# TPA6120A2_Headphone_Amp.net
KiCad netlist of a schematic drawn in Altium Designer
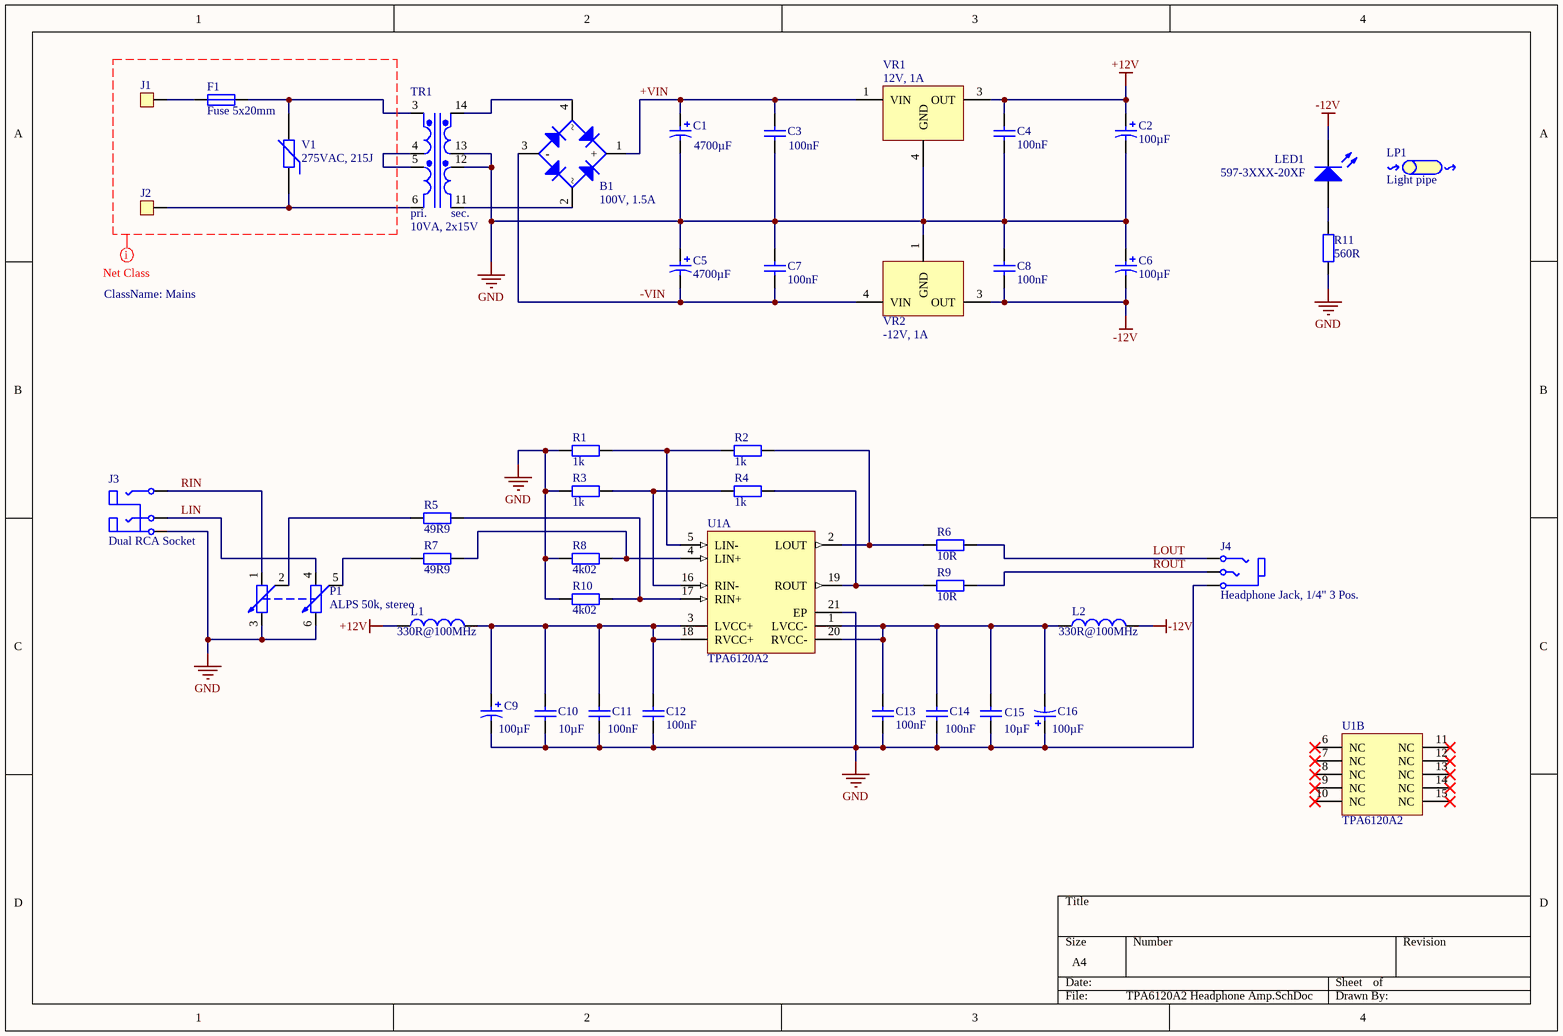
[diagram p0: TPA6120A2 Headphone Amp.SchDoc]

(export (version "E")
  (design (tool "Eeschema 10.0.6"))
  (components
    (comp (ref "B1")
      (value "100V, 1.5A")
      (footprint "WOG")
      (description "RECTIFIER BRIDGE 1.5A 100V WOG")
      (fields
        (field (name "PART NUMBER") "W01G-E4/51")
        (field (name "MANUFACTURER") "Vishay Semiconductor Diodes Division")
      )
      (libsource (lib "SVNDatabase_AK") (part "Bridge Rectifier"))
    )
    (comp (ref "C1")
      (value "4700µF")
      (footprint "CAP POL 16x25 RM 7.5MM")
      (description "CAP ALUM 4700UF 20% 25V RADIAL")
      (fields (field (name "PART NUMBER") "UVY1E472MHD") (field (name "MANUFACTURER") "Nichicon"))
      (libsource (lib "SVNDatabase_AK") (part "Cap Pol"))
    )
    (comp (ref "C2")
      (value "100µF")
      (footprint "cap pol 10x12.5mm rm 5mm")
      (description "CAP ALUM 100UF 20% 63V RADIAL")
      (fields
        (field (name "PART NUMBER") "EEU-FC1J101")
        (field (name "MANUFACTURER") "Panasonic Electronic Components")
      )
      (libsource (lib "SVNDatabase_AK") (part "Cap Pol"))
    )
    (comp (ref "C3")
      (value "100nF")
      (footprint "CAP0805_M")
      (description "CAP CER 0.1UF 50V 10% X7R 0805")
      (fields (field (name "PART NUMBER") "C0805C104K5RACTU") (field (name "MANUFACTURER") "Kemet"))
      (libsource (lib "SVNDatabase_AK") (part "CAP"))
    )
    (comp (ref "C4")
      (value "100nF")
      (footprint "CAP0805_M")
      (description "CAP CER 0.1UF 50V 10% X7R 0805")
      (fields (field (name "PART NUMBER") "C0805C104K5RACTU") (field (name "MANUFACTURER") "Kemet"))
      (libsource (lib "SVNDatabase_AK") (part "CAP"))
    )
    (comp (ref "C5")
      (value "4700µF")
      (footprint "CAP POL 16x25 RM 7.5MM")
      (description "CAP ALUM 4700UF 20% 25V RADIAL")
      (fields (field (name "PART NUMBER") "UVY1E472MHD") (field (name "MANUFACTURER") "Nichicon"))
      (libsource (lib "SVNDatabase_AK") (part "Cap Pol"))
    )
    (comp (ref "C6")
      (value "100µF")
      (footprint "cap pol 10x12.5mm rm 5mm")
      (description "CAP ALUM 100UF 20% 63V RADIAL")
      (fields
        (field (name "PART NUMBER") "EEU-FC1J101")
        (field (name "MANUFACTURER") "Panasonic Electronic Components")
      )
      (libsource (lib "SVNDatabase_AK") (part "Cap Pol"))
    )
    (comp (ref "C7")
      (value "100nF")
      (footprint "CAP0805_M")
      (description "CAP CER 0.1UF 50V 10% X7R 0805")
      (fields (field (name "PART NUMBER") "C0805C104K5RACTU") (field (name "MANUFACTURER") "Kemet"))
      (libsource (lib "SVNDatabase_AK") (part "CAP"))
    )
    (comp (ref "C8")
      (value "100nF")
      (footprint "CAP0805_M")
      (description "CAP CER 0.1UF 50V 10% X7R 0805")
      (fields (field (name "PART NUMBER") "C0805C104K5RACTU") (field (name "MANUFACTURER") "Kemet"))
      (libsource (lib "SVNDatabase_AK") (part "CAP"))
    )
    (comp (ref "C9")
      (value "100µF")
      (footprint "cap pol 10x12.5mm rm 5mm")
      (description "CAP ALUM 100UF 20% 63V RADIAL")
      (fields
        (field (name "PART NUMBER") "EEU-FC1J101")
        (field (name "MANUFACTURER") "Panasonic Electronic Components")
      )
      (libsource (lib "SVNDatabase_AK") (part "Cap Pol"))
    )
    (comp (ref "C10")
      (value "10µF")
      (footprint "CAP1210_M")
      (description "CAP CER 10UF 50V X7R 1210")
      (fields (field (name "PART NUMBER") "C1210C106K5RACTU") (field (name "MANUFACTURER") "Kemet"))
      (libsource (lib "SVNDatabase_AK") (part "CAP"))
    )
    (comp (ref "C11")
      (value "100nF")
      (footprint "CAP0805_M")
      (description "CAP CER 0.1UF 50V 10% X7R 0805")
      (fields (field (name "PART NUMBER") "C0805C104K5RACTU") (field (name "MANUFACTURER") "Kemet"))
      (libsource (lib "SVNDatabase_AK") (part "CAP"))
    )
    (comp (ref "C12")
      (value "100nF")
      (footprint "CAP0805_M")
      (description "CAP CER 0.1UF 50V 10% X7R 0805")
      (fields (field (name "PART NUMBER") "C0805C104K5RACTU") (field (name "MANUFACTURER") "Kemet"))
      (libsource (lib "SVNDatabase_AK") (part "CAP"))
    )
    (comp (ref "C13")
      (value "100nF")
      (footprint "CAP0805_M")
      (description "CAP CER 0.1UF 50V 10% X7R 0805")
      (fields (field (name "PART NUMBER") "C0805C104K5RACTU") (field (name "MANUFACTURER") "Kemet"))
      (libsource (lib "SVNDatabase_AK") (part "CAP"))
    )
    (comp (ref "C14")
      (value "100nF")
      (footprint "CAP0805_M")
      (description "CAP CER 0.1UF 50V 10% X7R 0805")
      (fields (field (name "PART NUMBER") "C0805C104K5RACTU") (field (name "MANUFACTURER") "Kemet"))
      (libsource (lib "SVNDatabase_AK") (part "CAP"))
    )
    (comp (ref "C15")
      (value "10µF")
      (footprint "CAP1210_M")
      (description "CAP CER 10UF 50V X7R 1210")
      (fields (field (name "PART NUMBER") "C1210C106K5RACTU") (field (name "MANUFACTURER") "Kemet"))
      (libsource (lib "SVNDatabase_AK") (part "CAP"))
    )
    (comp (ref "C16")
      (value "100µF")
      (footprint "cap pol 10x12.5mm rm 5mm")
      (description "CAP ALUM 100UF 20% 63V RADIAL")
      (fields
        (field (name "PART NUMBER") "EEU-FC1J101")
        (field (name "MANUFACTURER") "Panasonic Electronic Components")
      )
      (libsource (lib "SVNDatabase_AK") (part "Cap Pol"))
    )
    (comp (ref "F1")
      (value "Fuse 5x20mm")
      (footprint "0031.8201")
      (description "FUSE BLOK CARTRIDGE 500V 10A PCB")
      (fields (field (name "PART NUMBER") "0031.8201") (field (name "MANUFACTURER") "Schurter Inc."))
      (libsource (lib "SVNDatabase_AK") (part "Fuse"))
    )
    (comp (ref "J1")
      (value "~")
      (footprint "928814-1")
      (description "CONN QC TAB 0.250 SOLDER")
      (fields
        (field (name "PART NUMBER") "928814-1")
        (field (name "MANUFACTURER") "TE Connectivity AMP Connectors")
      )
      (libsource (lib "SVNDatabase_AK") (part "Header 1"))
    )
    (comp (ref "J2")
      (value "~")
      (footprint "928814-1")
      (description "CONN QC TAB 0.250 SOLDER")
      (fields
        (field (name "PART NUMBER") "928814-1")
        (field (name "MANUFACTURER") "TE Connectivity AMP Connectors")
      )
      (libsource (lib "SVNDatabase_AK") (part "Header 1"))
    )
    (comp (ref "J3")
      (value "Dual RCA Socket")
      (footprint "PJRAS1X2S__X")
      (description "PHONO JACK 2POS R/A RED/WHT")
      (fields (field (name "PART NUMBER") "PJRAS1X2S01X") (field (name "MANUFACTURER") "Switchcraft Inc."))
      (libsource (lib "SVNDatabase_AK") (part "Dual RCA Jack"))
    )
    (comp (ref "J4")
      (value "Headphone Jack, 1/4\" 3 Pos.")
      (footprint "RA49B")
      (description "CONN JACK R/A 3-COND DBL OPEN")
      (fields (field (name "PART NUMBER") "RA49B12B") (field (name "MANUFACTURER") "Switchcraft Inc."))
      (libsource (lib "SVNDatabase_AK") (part "Headphone Jack"))
    )
    (comp (ref "L1")
      (value "330R@100MHz")
      (footprint "INDC2012X14N")
      (description "FERRITE CHIP 330 OHM 2.5A 0805")
      (fields (field (name "PART NUMBER") "MPZ2012S331AT000") (field (name "MANUFACTURER") "TDK Corporation"))
      (libsource (lib "SVNDatabase_AK") (part "Inductor"))
    )
    (comp (ref "L2")
      (value "330R@100MHz")
      (footprint "INDC2012X14N")
      (description "FERRITE CHIP 330 OHM 2.5A 0805")
      (fields (field (name "PART NUMBER") "MPZ2012S331AT000") (field (name "MANUFACTURER") "TDK Corporation"))
      (libsource (lib "SVNDatabase_AK") (part "Inductor"))
    )
    (comp (ref "LED1")
      (value "597-3XXX-20XF")
      (footprint "597-3XXX-20XF")
      (description "LED RED CLEAR 2PLCC SMD")
      (fields (field (name "PART NUMBER") "597-3001-202F") (field (name "MANUFACTURER") "Dialight"))
      (libsource (lib "SVNDatabase_AK") (part "LED"))
    )
    (comp (ref "LP1")
      (value "Light pipe")
      (footprint "515-1049F")
      (description "LIGHT PIPE SGL ELEMENT")
      (fields (field (name "PART NUMBER") "5151049F") (field (name "MANUFACTURER") "Dialight"))
      (libsource (lib "SVNDatabase_AK") (part "Lightpipe"))
    )
    (comp (ref "P1")
      (value "ALPS 50k, stereo")
      (footprint "ALPS RK27112")
      (description "Pot, Stereo")
      (fields (field (name "PART NUMBER") "ALPS RK27112-F25-C0-A203"))
      (libsource (lib "SVNDatabase_AK") (part "Pot Stereo"))
    )
    (comp (ref "R1")
      (value "1k")
      (footprint "RES0805_M")
      (description "RES SMD 1K OHM 0.1% 1/8W 0805")
      (fields (field (name "PART NUMBER") "TNPW08051K00BEEA") (field (name "MANUFACTURER") "Vishay Dale"))
      (libsource (lib "SVNDatabase_AK") (part "RES"))
    )
    (comp (ref "R2")
      (value "1k")
      (footprint "RES1206_M")
      (description "RES SMD 1K OHM 0.1% 1/4W 1206")
      (fields (field (name "PART NUMBER") "TNPW12061K00BEEA") (field (name "MANUFACTURER") "Vishay Dale"))
      (libsource (lib "") (part "RES_2"))
    )
    (comp (ref "R3")
      (value "1k")
      (footprint "RES0805_M")
      (description "RES SMD 1K OHM 0.1% 1/8W 0805")
      (fields (field (name "PART NUMBER") "TNPW08051K00BEEA") (field (name "MANUFACTURER") "Vishay Dale"))
      (libsource (lib "SVNDatabase_AK") (part "RES"))
    )
    (comp (ref "R4")
      (value "1k")
      (footprint "RES1206_M")
      (description "RES SMD 1K OHM 0.1% 1/4W 1206")
      (fields (field (name "PART NUMBER") "TNPW12061K00BEEA") (field (name "MANUFACTURER") "Vishay Dale"))
      (libsource (lib "") (part "RES_2"))
    )
    (comp (ref "R5")
      (value "49R9")
      (footprint "RES0805_M")
      (description "RES SMD 49.9 OHM 0.1% 1/8W 0805")
      (fields (field (name "PART NUMBER") "TNPW080549R9BEEA") (field (name "MANUFACTURER") "Vishay Dale"))
      (libsource (lib "SVNDatabase_AK") (part "RES"))
    )
    (comp (ref "R6")
      (value "10R")
      (footprint "RES1206_M")
      (description "RES SMD 10 OHM 0.1% 0.4W 1206")
      (fields
        (field (name "PART NUMBER") "PAT1206E10R0BST1")
        (field (name "MANUFACTURER") "Vishay Thin Film")
      )
      (libsource (lib "SVNDatabase_AK") (part "RES"))
    )
    (comp (ref "R7")
      (value "49R9")
      (footprint "RES0805_M")
      (description "RES SMD 49.9 OHM 0.1% 1/8W 0805")
      (fields (field (name "PART NUMBER") "TNPW080549R9BEEA") (field (name "MANUFACTURER") "Vishay Dale"))
      (libsource (lib "SVNDatabase_AK") (part "RES"))
    )
    (comp (ref "R8")
      (value "4k02")
      (footprint "RES0805_M")
      (description "RES SMD 4.02K OHM 0.1% 1/5W 0805")
      (fields
        (field (name "PART NUMBER") "MCU0805MD4021BP100")
        (field (name "MANUFACTURER") "Vishay Beyschlag")
      )
      (libsource (lib "SVNDatabase_AK") (part "RES"))
    )
    (comp (ref "R9")
      (value "10R")
      (footprint "RES1206_M")
      (description "RES SMD 10 OHM 0.1% 0.4W 1206")
      (fields
        (field (name "PART NUMBER") "PAT1206E10R0BST1")
        (field (name "MANUFACTURER") "Vishay Thin Film")
      )
      (libsource (lib "SVNDatabase_AK") (part "RES"))
    )
    (comp (ref "R10")
      (value "4k02")
      (footprint "RES0805_M")
      (description "RES SMD 4.02K OHM 0.1% 1/5W 0805")
      (fields
        (field (name "PART NUMBER") "MCU0805MD4021BP100")
        (field (name "MANUFACTURER") "Vishay Beyschlag")
      )
      (libsource (lib "SVNDatabase_AK") (part "RES"))
    )
    (comp (ref "R11")
      (value "560R")
      (footprint "RES1206_M")
      (description "RES SMD 560 OHM 1% 1/2W 1206")
      (fields (field (name "PART NUMBER") "CRCW1206560RFKEAHP") (field (name "MANUFACTURER") "Vishay Dale"))
      (libsource (lib "") (part "RES_1"))
    )
    (comp (ref "TR1")
      (value "10VA, 2x15V")
      (footprint "Talema 10VA")
      (description "XFRMR TOROIDAL 10VA THRU HOLE")
      (fields
        (field (name "PART NUMBER") "Talema 70043k")
        (field (name "MANUFACTURER") "Acme Electric/Amveco/Actown")
      )
      (libsource (lib "SVNDatabase_AK") (part "Talema 70000 series"))
    )
    (comp (ref "U1")
      (value "TPA6120A2")
      (footprint "TI-DWP20-3730X2350TP_N")
      (description "IC AMP AUDIO .08W HIFI 20SOPWR")
      (fields (field (name "PART NUMBER") "TPA6120A2DWPR") (field (name "MANUFACTURER") "Texas Instruments"))
      (libsource (lib "SVNDatabase_AK") (part "TPA6120A2_DWP20"))
    )
    (comp (ref "V1")
      (value "275VAC, 215J")
      (footprint "S20K275E2")
      (description "VARISTOR 387V 10KA DISC 20MM")
      (fields (field (name "PART NUMBER") "S20K275E2") (field (name "MANUFACTURER") "EPCOS (TDK)"))
      (libsource (lib "SVNDatabase_AK") (part "Varistor"))
    )
    (comp (ref "VR1")
      (value "12V, 1A")
      (footprint "D2PAK")
      (description "IC REG LDO 12V 1.5A D2PAK")
      (fields (field (name "PART NUMBER") "7812") (field (name "MANUFACTURER") "STMicroelectronics"))
      (libsource (lib "SVNDatabase_AK") (part "VREG_POS_D2PAK"))
    )
    (comp (ref "VR2")
      (value "-12V, 1A")
      (footprint "D2PAK")
      (description "IC REG LDO -12V 1.5A D2PAK")
      (fields (field (name "PART NUMBER") "7912") (field (name "MANUFACTURER") "STMicroelectronics"))
      (libsource (lib "SVNDatabase_AK") (part "VREG_NEG_D2PAK"))
    )
  )
  (nets
    (net (code "1") (name "+12V") (class "Default")
      (node (ref "C2") (pin "1") (pinfunction "1_1") (pintype "passive"))
      (node (ref "C4") (pin "2") (pinfunction "2_2") (pintype "passive"))
      (node (ref "L1") (pin "1") (pinfunction "1_1") (pintype "passive"))
      (node (ref "VR1") (pin "3") (pinfunction "OUT_3") (pintype "power_in"))
    )
    (net (code "2") (name "-12V") (class "Default")
      (node (ref "C6") (pin "2") (pinfunction "2_2") (pintype "passive"))
      (node (ref "C8") (pin "1") (pinfunction "1_1") (pintype "passive"))
      (node (ref "L2") (pin "2") (pinfunction "2_2") (pintype "passive"))
      (node (ref "LED1") (pin "2") (pinfunction "K_2") (pintype "passive"))
      (node (ref "VR2") (pin "3") (pinfunction "OUT_3") (pintype "power_in"))
    )
    (net (code "3") (name "/+VIN") (class "Default")
      (node (ref "B1") (pin "1") (pinfunction "+_1") (pintype "passive"))
      (node (ref "C1") (pin "1") (pinfunction "1_1") (pintype "passive"))
      (node (ref "C3") (pin "2") (pinfunction "2_2") (pintype "passive"))
      (node (ref "VR1") (pin "1") (pinfunction "VIN_1") (pintype "power_in"))
    )
    (net (code "4") (name "/-VIN") (class "Default")
      (node (ref "B1") (pin "3") (pinfunction "-_3") (pintype "passive"))
      (node (ref "C5") (pin "2") (pinfunction "2_2") (pintype "passive"))
      (node (ref "C7") (pin "1") (pinfunction "1_1") (pintype "passive"))
      (node (ref "VR2") (pin "4") (pinfunction "VIN_4") (pintype "power_in"))
    )
    (net (code "5") (name "/LIN") (class "Default")
      (node (ref "J3") (pin "1") (pinfunction "1_1") (pintype "passive"))
      (node (ref "P1") (pin "4") (pinfunction "4_4") (pintype "passive"))
    )
    (net (code "6") (name "/LOUT") (class "Default")
      (node (ref "J4") (pin "2") (pinfunction "2_2") (pintype "passive"))
      (node (ref "R6") (pin "2") (pinfunction "2_2") (pintype "passive"))
    )
    (net (code "7") (name "/RIN") (class "Default")
      (node (ref "J3") (pin "2") (pinfunction "2_2") (pintype "passive"))
      (node (ref "P1") (pin "1") (pinfunction "1_1") (pintype "passive"))
    )
    (net (code "8") (name "/ROUT") (class "Default")
      (node (ref "J4") (pin "3") (pinfunction "3_3") (pintype "passive"))
      (node (ref "R9") (pin "2") (pinfunction "2_2") (pintype "passive"))
    )
    (net (code "9") (name "GND") (class "Default")
      (node (ref "C1") (pin "2") (pinfunction "2_2") (pintype "passive"))
      (node (ref "C10") (pin "1") (pinfunction "1_1") (pintype "passive"))
      (node (ref "C11") (pin "1") (pinfunction "1_1") (pintype "passive"))
      (node (ref "C12") (pin "1") (pinfunction "1_1") (pintype "passive"))
      (node (ref "C13") (pin "1") (pinfunction "1_1") (pintype "passive"))
      (node (ref "C14") (pin "1") (pinfunction "1_1") (pintype "passive"))
      (node (ref "C15") (pin "1") (pinfunction "1_1") (pintype "passive"))
      (node (ref "C16") (pin "1") (pinfunction "1_1") (pintype "passive"))
      (node (ref "C2") (pin "2") (pinfunction "2_2") (pintype "passive"))
      (node (ref "C3") (pin "1") (pinfunction "1_1") (pintype "passive"))
      (node (ref "C4") (pin "1") (pinfunction "1_1") (pintype "passive"))
      (node (ref "C5") (pin "1") (pinfunction "1_1") (pintype "passive"))
      (node (ref "C6") (pin "1") (pinfunction "1_1") (pintype "passive"))
      (node (ref "C7") (pin "2") (pinfunction "2_2") (pintype "passive"))
      (node (ref "C8") (pin "2") (pinfunction "2_2") (pintype "passive"))
      (node (ref "C9") (pin "2") (pinfunction "2_2") (pintype "passive"))
      (node (ref "J3") (pin "3") (pinfunction "3_3") (pintype "passive"))
      (node (ref "J4") (pin "1") (pinfunction "1_1") (pintype "passive"))
      (node (ref "P1") (pin "3") (pinfunction "3_3") (pintype "passive"))
      (node (ref "P1") (pin "6") (pinfunction "6_6") (pintype "passive"))
      (node (ref "R1") (pin "1") (pinfunction "1_1") (pintype "passive"))
      (node (ref "R10") (pin "1") (pinfunction "1_1") (pintype "passive"))
      (node (ref "R11") (pin "2") (pinfunction "2_2") (pintype "passive"))
      (node (ref "R3") (pin "1") (pinfunction "1_1") (pintype "passive"))
      (node (ref "R8") (pin "1") (pinfunction "1_1") (pintype "passive"))
      (node (ref "TR1") (pin "12") (pinfunction "Sek1-_12") (pintype "passive"))
      (node (ref "TR1") (pin "13") (pinfunction "Sek2+_13") (pintype "passive"))
      (node (ref "U1") (pin "21") (pinfunction "EP_21") (pintype "power_in"))
      (node (ref "VR1") (pin "4") (pinfunction "GND_4") (pintype "power_in"))
      (node (ref "VR2") (pin "1") (pinfunction "GND_1") (pintype "power_in"))
    )
    (net (code "10") (name "Net-(F1-Pad1)") (class "Default")
      (node (ref "F1") (pin "1") (pinfunction "1_1") (pintype "passive"))
      (node (ref "J1") (pin "1") (pinfunction "1_1") (pintype "passive"))
    )
    (net (code "11") (name "Net-(LED1-A)") (class "Default")
      (node (ref "LED1") (pin "1") (pinfunction "A_1") (pintype "passive"))
      (node (ref "R11") (pin "1") (pinfunction "1_1") (pintype "passive"))
    )
    (net (code "12") (name "Net-(P1-Pad2)") (class "Default")
      (node (ref "P1") (pin "2") (pinfunction "2_2") (pintype "power_in"))
      (node (ref "R5") (pin "1") (pinfunction "1_1") (pintype "passive"))
    )
    (net (code "13") (name "Net-(P1-Pad5)") (class "Default")
      (node (ref "P1") (pin "5") (pinfunction "5_5") (pintype "power_in"))
      (node (ref "R7") (pin "1") (pinfunction "1_1") (pintype "passive"))
    )
    (net (code "14") (name "Net-(TR1-Pri1+)") (class "Default")
      (node (ref "J2") (pin "1") (pinfunction "1_1") (pintype "passive"))
      (node (ref "TR1") (pin "6") (pinfunction "Pri1+_6") (pintype "passive"))
      (node (ref "V1") (pin "1") (pinfunction "1_1") (pintype "passive"))
    )
    (net (code "15") (name "Net-(TR1-Pri1-)") (class "Default")
      (node (ref "TR1") (pin "4") (pinfunction "Pri2+_4") (pintype "passive"))
      (node (ref "TR1") (pin "5") (pinfunction "Pri1-_5") (pintype "passive"))
    )
    (net (code "16") (name "Net-(TR1-Pri2-)") (class "Default")
      (node (ref "F1") (pin "2") (pinfunction "2_2") (pintype "passive"))
      (node (ref "TR1") (pin "3") (pinfunction "Pri2-_3") (pintype "passive"))
      (node (ref "V1") (pin "2") (pinfunction "2_2") (pintype "passive"))
    )
    (net (code "17") (name "Net-(TR1-Sek1+)") (class "Default")
      (node (ref "B1") (pin "2") (pinfunction "~_2") (pintype "passive"))
      (node (ref "TR1") (pin "11") (pinfunction "Sek1+_11") (pintype "passive"))
    )
    (net (code "18") (name "Net-(TR1-Sek2-)") (class "Default")
      (node (ref "B1") (pin "4") (pinfunction "~_4") (pintype "passive"))
      (node (ref "TR1") (pin "14") (pinfunction "Sek2-_14") (pintype "passive"))
    )
    (net (code "19") (name "Net-(U1A-LIN+)") (class "Default")
      (node (ref "R7") (pin "2") (pinfunction "2_2") (pintype "passive"))
      (node (ref "R8") (pin "2") (pinfunction "2_2") (pintype "passive"))
      (node (ref "U1") (pin "4") (pinfunction "LIN+_4") (pintype "input"))
    )
    (net (code "20") (name "Net-(U1A-LIN-)") (class "Default")
      (node (ref "R1") (pin "2") (pinfunction "2_2") (pintype "passive"))
      (node (ref "R2") (pin "2") (pinfunction "2_2") (pintype "passive"))
      (node (ref "U1") (pin "5") (pinfunction "LIN-_5") (pintype "input"))
    )
    (net (code "21") (name "Net-(U1A-LOUT)") (class "Default")
      (node (ref "R2") (pin "1") (pinfunction "1_1") (pintype "passive"))
      (node (ref "R6") (pin "1") (pinfunction "1_1") (pintype "passive"))
      (node (ref "U1") (pin "2") (pinfunction "LOUT_2") (pintype "output"))
    )
    (net (code "22") (name "Net-(U1A-LVCC+)") (class "Default")
      (node (ref "C10") (pin "2") (pinfunction "2_2") (pintype "passive"))
      (node (ref "C11") (pin "2") (pinfunction "2_2") (pintype "passive"))
      (node (ref "C12") (pin "2") (pinfunction "2_2") (pintype "passive"))
      (node (ref "C9") (pin "1") (pinfunction "1_1") (pintype "passive"))
      (node (ref "L1") (pin "2") (pinfunction "2_2") (pintype "passive"))
      (node (ref "U1") (pin "18") (pinfunction "RVCC+_18") (pintype "power_in"))
      (node (ref "U1") (pin "3") (pinfunction "LVCC+_3") (pintype "power_in"))
    )
    (net (code "23") (name "Net-(U1A-LVCC-)") (class "Default")
      (node (ref "C13") (pin "2") (pinfunction "2_2") (pintype "passive"))
      (node (ref "C14") (pin "2") (pinfunction "2_2") (pintype "passive"))
      (node (ref "C15") (pin "2") (pinfunction "2_2") (pintype "passive"))
      (node (ref "C16") (pin "2") (pinfunction "2_2") (pintype "passive"))
      (node (ref "L2") (pin "1") (pinfunction "1_1") (pintype "passive"))
      (node (ref "U1") (pin "1") (pinfunction "LVCC-_1") (pintype "power_in"))
      (node (ref "U1") (pin "20") (pinfunction "RVCC-_20") (pintype "power_in"))
    )
    (net (code "24") (name "Net-(U1A-RIN+)") (class "Default")
      (node (ref "R10") (pin "2") (pinfunction "2_2") (pintype "passive"))
      (node (ref "R5") (pin "2") (pinfunction "2_2") (pintype "passive"))
      (node (ref "U1") (pin "17") (pinfunction "RIN+_17") (pintype "input"))
    )
    (net (code "25") (name "Net-(U1A-RIN-)") (class "Default")
      (node (ref "R3") (pin "2") (pinfunction "2_2") (pintype "passive"))
      (node (ref "R4") (pin "2") (pinfunction "2_2") (pintype "passive"))
      (node (ref "U1") (pin "16") (pinfunction "RIN-_16") (pintype "input"))
    )
    (net (code "26") (name "Net-(U1A-ROUT)") (class "Default")
      (node (ref "R4") (pin "1") (pinfunction "1_1") (pintype "passive"))
      (node (ref "R9") (pin "1") (pinfunction "1_1") (pintype "passive"))
      (node (ref "U1") (pin "19") (pinfunction "ROUT_19") (pintype "output"))
    )
    (net (code "27") (name "unconnected-(U1B-NC-Pad6)") (class "Default")
      (node (ref "U1") (pin "6") (pinfunction "NC_6") (pintype "passive+no_connect"))
    )
    (net (code "28") (name "unconnected-(U1B-NC-Pad7)") (class "Default")
      (node (ref "U1") (pin "7") (pinfunction "NC_7") (pintype "passive+no_connect"))
    )
    (net (code "29") (name "unconnected-(U1B-NC-Pad8)") (class "Default")
      (node (ref "U1") (pin "8") (pinfunction "NC_8") (pintype "passive+no_connect"))
    )
    (net (code "30") (name "unconnected-(U1B-NC-Pad9)") (class "Default")
      (node (ref "U1") (pin "9") (pinfunction "NC_9") (pintype "passive+no_connect"))
    )
    (net (code "31") (name "unconnected-(U1B-NC-Pad10)") (class "Default")
      (node (ref "U1") (pin "10") (pinfunction "NC_10") (pintype "passive+no_connect"))
    )
    (net (code "32") (name "unconnected-(U1B-NC-Pad11)") (class "Default")
      (node (ref "U1") (pin "11") (pinfunction "NC_11") (pintype "passive+no_connect"))
    )
    (net (code "33") (name "unconnected-(U1B-NC-Pad12)") (class "Default")
      (node (ref "U1") (pin "12") (pinfunction "NC_12") (pintype "passive+no_connect"))
    )
    (net (code "34") (name "unconnected-(U1B-NC-Pad13)") (class "Default")
      (node (ref "U1") (pin "13") (pinfunction "NC_13") (pintype "passive+no_connect"))
    )
    (net (code "35") (name "unconnected-(U1B-NC-Pad14)") (class "Default")
      (node (ref "U1") (pin "14") (pinfunction "NC_14") (pintype "passive+no_connect"))
    )
    (net (code "36") (name "unconnected-(U1B-NC-Pad15)") (class "Default")
      (node (ref "U1") (pin "15") (pinfunction "NC_15") (pintype "passive+no_connect"))
    )
  )
)
